# 19_-CAMERA_PWR_CONNECTORS.net
KiCad netlist of a schematic drawn in Altium Designer
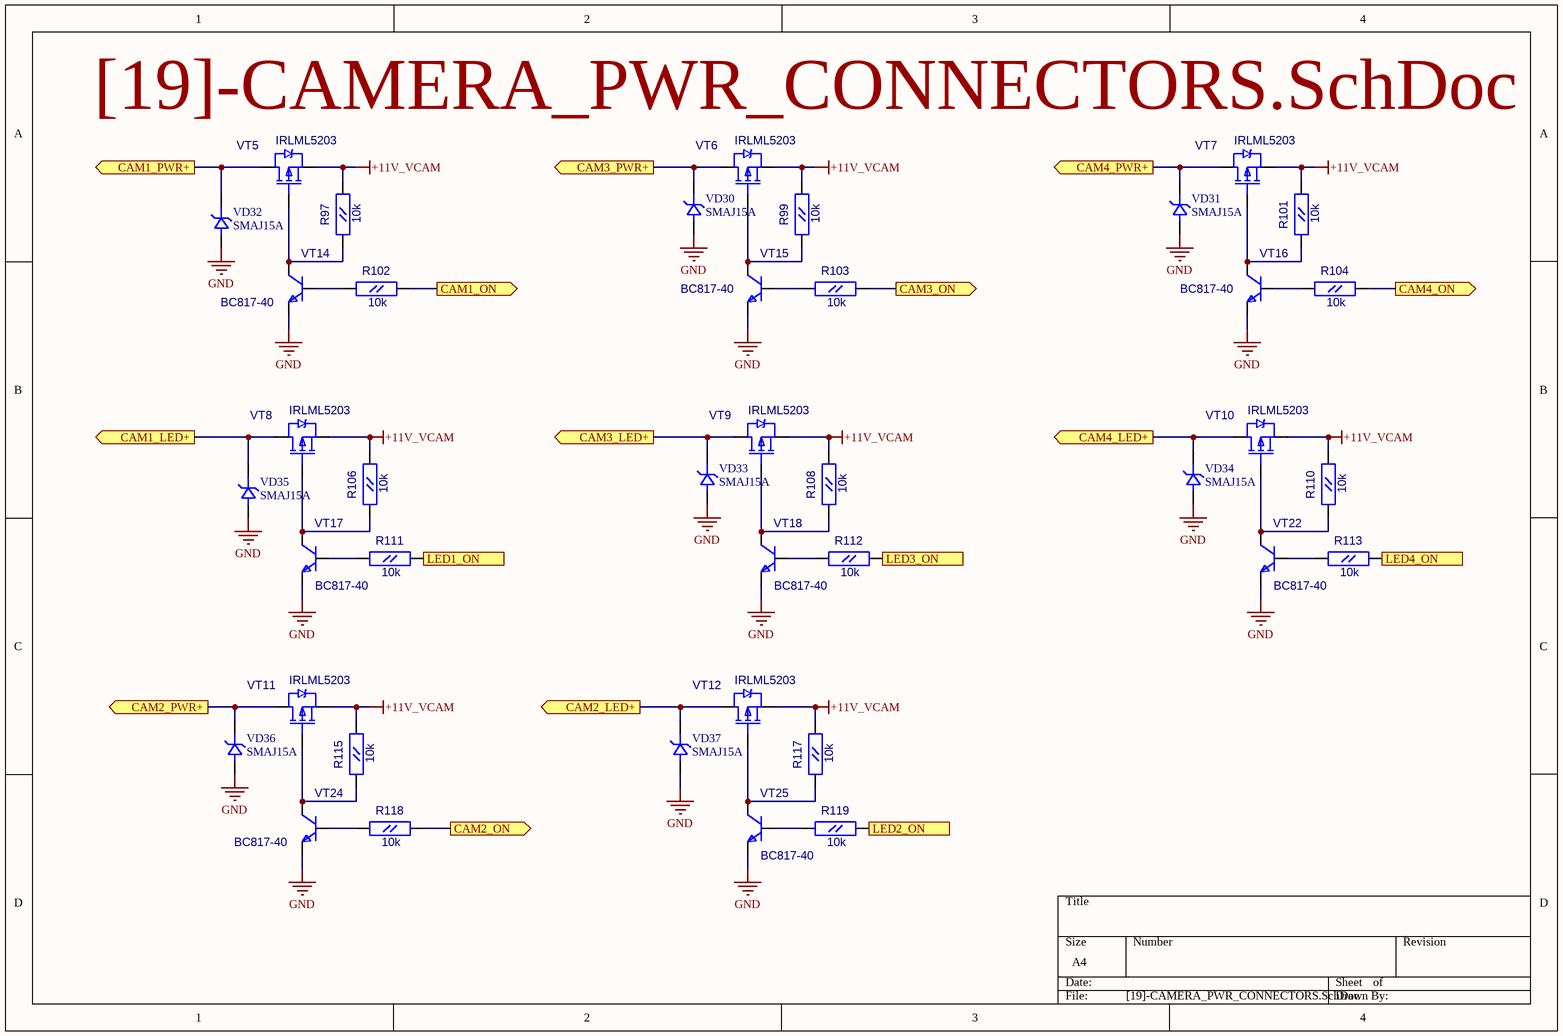
[diagram p0: [19]-CAMERA_PWR_CONNECTORS.SchDoc]

(export (version "E")
  (design (tool "Eeschema 10.0.6"))
  (components
    (comp (ref "R97")
      (value "10k")
      (footprint "RC0603")
      (description "RC0603")
      (libsource (lib "fizik_lib") (part "RC0603"))
    )
    (comp (ref "R99")
      (value "10k")
      (footprint "RC0603")
      (description "RC0603")
      (libsource (lib "fizik_lib") (part "RC0603"))
    )
    (comp (ref "R101")
      (value "10k")
      (footprint "RC0603")
      (description "RC0603")
      (libsource (lib "fizik_lib") (part "RC0603"))
    )
    (comp (ref "R102")
      (value "10k")
      (footprint "RC0603")
      (description "RC0603")
      (libsource (lib "fizik_lib") (part "RC0603"))
    )
    (comp (ref "R103")
      (value "10k")
      (footprint "RC0603")
      (description "RC0603")
      (libsource (lib "fizik_lib") (part "RC0603"))
    )
    (comp (ref "R104")
      (value "10k")
      (footprint "RC0603")
      (description "RC0603")
      (libsource (lib "fizik_lib") (part "RC0603"))
    )
    (comp (ref "R106")
      (value "10k")
      (footprint "RC0603")
      (description "RC0603")
      (libsource (lib "fizik_lib") (part "RC0603"))
    )
    (comp (ref "R108")
      (value "10k")
      (footprint "RC0603")
      (description "RC0603")
      (libsource (lib "fizik_lib") (part "RC0603"))
    )
    (comp (ref "R110")
      (value "10k")
      (footprint "RC0603")
      (description "RC0603")
      (libsource (lib "fizik_lib") (part "RC0603"))
    )
    (comp (ref "R111")
      (value "10k")
      (footprint "RC0603")
      (description "RC0603")
      (libsource (lib "fizik_lib") (part "RC0603"))
    )
    (comp (ref "R112")
      (value "10k")
      (footprint "RC0603")
      (description "RC0603")
      (libsource (lib "fizik_lib") (part "RC0603"))
    )
    (comp (ref "R113")
      (value "10k")
      (footprint "RC0603")
      (description "RC0603")
      (libsource (lib "fizik_lib") (part "RC0603"))
    )
    (comp (ref "R115")
      (value "10k")
      (footprint "RC0603")
      (description "RC0603")
      (libsource (lib "fizik_lib") (part "RC0603"))
    )
    (comp (ref "R117")
      (value "10k")
      (footprint "RC0603")
      (description "RC0603")
      (libsource (lib "fizik_lib") (part "RC0603"))
    )
    (comp (ref "R118")
      (value "10k")
      (footprint "RC0603")
      (description "RC0603")
      (libsource (lib "fizik_lib") (part "RC0603"))
    )
    (comp (ref "R119")
      (value "10k")
      (footprint "RC0603")
      (description "RC0603")
      (libsource (lib "fizik_lib") (part "RC0603"))
    )
    (comp (ref "VD30") (value "SMAJ15A") (footprint "SMA") (libsource (lib "fizik_lib (1)") (part "SMAJ")))
    (comp (ref "VD31") (value "SMAJ15A") (footprint "SMA") (libsource (lib "fizik_lib (1)") (part "SMAJ")))
    (comp (ref "VD32") (value "SMAJ15A") (footprint "SMA") (libsource (lib "fizik_lib (1)") (part "SMAJ")))
    (comp (ref "VD33") (value "SMAJ15A") (footprint "SMA") (libsource (lib "fizik_lib (1)") (part "SMAJ")))
    (comp (ref "VD34") (value "SMAJ15A") (footprint "SMA") (libsource (lib "fizik_lib (1)") (part "SMAJ")))
    (comp (ref "VD35") (value "SMAJ15A") (footprint "SMA") (libsource (lib "fizik_lib (1)") (part "SMAJ")))
    (comp (ref "VD36") (value "SMAJ15A") (footprint "SMA") (libsource (lib "fizik_lib (1)") (part "SMAJ")))
    (comp (ref "VD37") (value "SMAJ15A") (footprint "SMA") (libsource (lib "fizik_lib (1)") (part "SMAJ")))
    (comp (ref "VT5")
      (value "IRLML5203")
      (footprint "SOT-23(123)")
      (description "HEXFET Power MOSFET")
      (libsource (lib "fizik_lib (1)") (part "IRLML6402"))
    )
    (comp (ref "VT6")
      (value "IRLML5203")
      (footprint "SOT-23(123)")
      (description "HEXFET Power MOSFET")
      (libsource (lib "fizik_lib (1)") (part "IRLML6402"))
    )
    (comp (ref "VT7")
      (value "IRLML5203")
      (footprint "SOT-23(123)")
      (description "HEXFET Power MOSFET")
      (libsource (lib "fizik_lib (1)") (part "IRLML6402"))
    )
    (comp (ref "VT8")
      (value "IRLML5203")
      (footprint "SOT-23(123)")
      (description "HEXFET Power MOSFET")
      (libsource (lib "fizik_lib (1)") (part "IRLML6402"))
    )
    (comp (ref "VT9")
      (value "IRLML5203")
      (footprint "SOT-23(123)")
      (description "HEXFET Power MOSFET")
      (libsource (lib "fizik_lib (1)") (part "IRLML6402"))
    )
    (comp (ref "VT10")
      (value "IRLML5203")
      (footprint "SOT-23(123)")
      (description "HEXFET Power MOSFET")
      (libsource (lib "fizik_lib (1)") (part "IRLML6402"))
    )
    (comp (ref "VT11")
      (value "IRLML5203")
      (footprint "SOT-23(123)")
      (description "HEXFET Power MOSFET")
      (libsource (lib "fizik_lib (1)") (part "IRLML6402"))
    )
    (comp (ref "VT12")
      (value "IRLML5203")
      (footprint "SOT-23(123)")
      (description "HEXFET Power MOSFET")
      (libsource (lib "fizik_lib (1)") (part "IRLML6402"))
    )
    (comp (ref "VT14")
      (value "BC817-40")
      (footprint "SOT-23(123)")
      (description "NPN 500ma transistor")
      (libsource (lib "fizik_lib") (part "BC846BLT1"))
    )
    (comp (ref "VT15")
      (value "BC817-40")
      (footprint "SOT-23(123)")
      (description "NPN 500ma transistor")
      (libsource (lib "fizik_lib") (part "BC846BLT1"))
    )
    (comp (ref "VT16")
      (value "BC817-40")
      (footprint "SOT-23(123)")
      (description "NPN 500ma transistor")
      (libsource (lib "fizik_lib") (part "BC846BLT1"))
    )
    (comp (ref "VT17")
      (value "BC817-40")
      (footprint "SOT-23(123)")
      (description "NPN 500ma transistor")
      (libsource (lib "fizik_lib") (part "BC846BLT1"))
    )
    (comp (ref "VT18")
      (value "BC817-40")
      (footprint "SOT-23(123)")
      (description "NPN 500ma transistor")
      (libsource (lib "fizik_lib") (part "BC846BLT1"))
    )
    (comp (ref "VT22")
      (value "BC817-40")
      (footprint "SOT-23(123)")
      (description "NPN 500ma transistor")
      (libsource (lib "fizik_lib") (part "BC846BLT1"))
    )
    (comp (ref "VT24")
      (value "BC817-40")
      (footprint "SOT-23(123)")
      (description "NPN 500ma transistor")
      (libsource (lib "fizik_lib") (part "BC846BLT1"))
    )
    (comp (ref "VT25")
      (value "BC817-40")
      (footprint "SOT-23(123)")
      (description "NPN 500ma transistor")
      (libsource (lib "fizik_lib") (part "BC846BLT1"))
    )
  )
  (nets
    (net (code "1") (name "+11V_VCAM") (class "Default")
      (node (ref "R101") (pin "2") (pinfunction "B_2") (pintype "passive"))
      (node (ref "R106") (pin "2") (pinfunction "B_2") (pintype "passive"))
      (node (ref "R108") (pin "2") (pinfunction "B_2") (pintype "passive"))
      (node (ref "R110") (pin "2") (pinfunction "B_2") (pintype "passive"))
      (node (ref "R115") (pin "2") (pinfunction "B_2") (pintype "passive"))
      (node (ref "R117") (pin "2") (pinfunction "B_2") (pintype "passive"))
      (node (ref "R97") (pin "2") (pinfunction "B_2") (pintype "passive"))
      (node (ref "R99") (pin "2") (pinfunction "B_2") (pintype "passive"))
      (node (ref "VT10") (pin "2") (pinfunction "S_2") (pintype "passive"))
      (node (ref "VT11") (pin "2") (pinfunction "S_2") (pintype "passive"))
      (node (ref "VT12") (pin "2") (pinfunction "S_2") (pintype "passive"))
      (node (ref "VT5") (pin "2") (pinfunction "S_2") (pintype "passive"))
      (node (ref "VT6") (pin "2") (pinfunction "S_2") (pintype "passive"))
      (node (ref "VT7") (pin "2") (pinfunction "S_2") (pintype "passive"))
      (node (ref "VT8") (pin "2") (pinfunction "S_2") (pintype "passive"))
      (node (ref "VT9") (pin "2") (pinfunction "S_2") (pintype "passive"))
    )
    (net (code "2") (name "/CAM1_LED+") (class "Default")
      (node (ref "VD35") (pin "2") (pinfunction "K_2") (pintype "passive"))
      (node (ref "VT8") (pin "3") (pinfunction "D_3") (pintype "passive"))
    )
    (net (code "3") (name "/CAM1_ON") (class "Default")
      (node (ref "R102") (pin "2") (pinfunction "B_2") (pintype "passive"))
    )
    (net (code "4") (name "/CAM1_PWR+") (class "Default")
      (node (ref "VD32") (pin "2") (pinfunction "K_2") (pintype "passive"))
      (node (ref "VT5") (pin "3") (pinfunction "D_3") (pintype "passive"))
    )
    (net (code "5") (name "/CAM2_LED+") (class "Default")
      (node (ref "VD37") (pin "2") (pinfunction "K_2") (pintype "passive"))
      (node (ref "VT12") (pin "3") (pinfunction "D_3") (pintype "passive"))
    )
    (net (code "6") (name "/CAM2_ON") (class "Default")
      (node (ref "R118") (pin "2") (pinfunction "B_2") (pintype "passive"))
    )
    (net (code "7") (name "/CAM2_PWR+") (class "Default")
      (node (ref "VD36") (pin "2") (pinfunction "K_2") (pintype "passive"))
      (node (ref "VT11") (pin "3") (pinfunction "D_3") (pintype "passive"))
    )
    (net (code "8") (name "/CAM3_LED+") (class "Default")
      (node (ref "VD33") (pin "2") (pinfunction "K_2") (pintype "passive"))
      (node (ref "VT9") (pin "3") (pinfunction "D_3") (pintype "passive"))
    )
    (net (code "9") (name "/CAM3_ON") (class "Default")
      (node (ref "R103") (pin "2") (pinfunction "B_2") (pintype "passive"))
    )
    (net (code "10") (name "/CAM3_PWR+") (class "Default")
      (node (ref "VD30") (pin "2") (pinfunction "K_2") (pintype "passive"))
      (node (ref "VT6") (pin "3") (pinfunction "D_3") (pintype "passive"))
    )
    (net (code "11") (name "/CAM4_LED+") (class "Default")
      (node (ref "VD34") (pin "2") (pinfunction "K_2") (pintype "passive"))
      (node (ref "VT10") (pin "3") (pinfunction "D_3") (pintype "passive"))
    )
    (net (code "12") (name "/CAM4_ON") (class "Default")
      (node (ref "R104") (pin "2") (pinfunction "B_2") (pintype "passive"))
    )
    (net (code "13") (name "/CAM4_PWR+") (class "Default")
      (node (ref "VD31") (pin "2") (pinfunction "K_2") (pintype "passive"))
      (node (ref "VT7") (pin "3") (pinfunction "D_3") (pintype "passive"))
    )
    (net (code "14") (name "/LED1_ON") (class "Default")
      (node (ref "R111") (pin "2") (pinfunction "B_2") (pintype "passive"))
    )
    (net (code "15") (name "/LED2_ON") (class "Default")
      (node (ref "R119") (pin "2") (pinfunction "B_2") (pintype "passive"))
    )
    (net (code "16") (name "/LED3_ON") (class "Default")
      (node (ref "R112") (pin "2") (pinfunction "B_2") (pintype "passive"))
    )
    (net (code "17") (name "/LED4_ON") (class "Default")
      (node (ref "R113") (pin "2") (pinfunction "B_2") (pintype "passive"))
    )
    (net (code "18") (name "GND") (class "Default")
      (node (ref "VD30") (pin "1") (pinfunction "A_1") (pintype "passive"))
      (node (ref "VD31") (pin "1") (pinfunction "A_1") (pintype "passive"))
      (node (ref "VD32") (pin "1") (pinfunction "A_1") (pintype "passive"))
      (node (ref "VD33") (pin "1") (pinfunction "A_1") (pintype "passive"))
      (node (ref "VD34") (pin "1") (pinfunction "A_1") (pintype "passive"))
      (node (ref "VD35") (pin "1") (pinfunction "A_1") (pintype "passive"))
      (node (ref "VD36") (pin "1") (pinfunction "A_1") (pintype "passive"))
      (node (ref "VD37") (pin "1") (pinfunction "A_1") (pintype "passive"))
      (node (ref "VT14") (pin "2") (pinfunction "E_2") (pintype "passive"))
      (node (ref "VT15") (pin "2") (pinfunction "E_2") (pintype "passive"))
      (node (ref "VT16") (pin "2") (pinfunction "E_2") (pintype "passive"))
      (node (ref "VT17") (pin "2") (pinfunction "E_2") (pintype "passive"))
      (node (ref "VT18") (pin "2") (pinfunction "E_2") (pintype "passive"))
      (node (ref "VT22") (pin "2") (pinfunction "E_2") (pintype "passive"))
      (node (ref "VT24") (pin "2") (pinfunction "E_2") (pintype "passive"))
      (node (ref "VT25") (pin "2") (pinfunction "E_2") (pintype "passive"))
    )
    (net (code "19") (name "Net-(R97-A)") (class "Default")
      (node (ref "R97") (pin "1") (pinfunction "A_1") (pintype "passive"))
      (node (ref "VT14") (pin "3") (pinfunction "C_3") (pintype "passive"))
      (node (ref "VT5") (pin "1") (pinfunction "G_1") (pintype "passive"))
    )
    (net (code "20") (name "Net-(R99-A)") (class "Default")
      (node (ref "R99") (pin "1") (pinfunction "A_1") (pintype "passive"))
      (node (ref "VT15") (pin "3") (pinfunction "C_3") (pintype "passive"))
      (node (ref "VT6") (pin "1") (pinfunction "G_1") (pintype "passive"))
    )
    (net (code "21") (name "Net-(R101-A)") (class "Default")
      (node (ref "R101") (pin "1") (pinfunction "A_1") (pintype "passive"))
      (node (ref "VT16") (pin "3") (pinfunction "C_3") (pintype "passive"))
      (node (ref "VT7") (pin "1") (pinfunction "G_1") (pintype "passive"))
    )
    (net (code "22") (name "Net-(R102-A)") (class "Default")
      (node (ref "R102") (pin "1") (pinfunction "A_1") (pintype "passive"))
      (node (ref "VT14") (pin "1") (pinfunction "B_1") (pintype "passive"))
    )
    (net (code "23") (name "Net-(R103-A)") (class "Default")
      (node (ref "R103") (pin "1") (pinfunction "A_1") (pintype "passive"))
      (node (ref "VT15") (pin "1") (pinfunction "B_1") (pintype "passive"))
    )
    (net (code "24") (name "Net-(R104-A)") (class "Default")
      (node (ref "R104") (pin "1") (pinfunction "A_1") (pintype "passive"))
      (node (ref "VT16") (pin "1") (pinfunction "B_1") (pintype "passive"))
    )
    (net (code "25") (name "Net-(R106-A)") (class "Default")
      (node (ref "R106") (pin "1") (pinfunction "A_1") (pintype "passive"))
      (node (ref "VT17") (pin "3") (pinfunction "C_3") (pintype "passive"))
      (node (ref "VT8") (pin "1") (pinfunction "G_1") (pintype "passive"))
    )
    (net (code "26") (name "Net-(R108-A)") (class "Default")
      (node (ref "R108") (pin "1") (pinfunction "A_1") (pintype "passive"))
      (node (ref "VT18") (pin "3") (pinfunction "C_3") (pintype "passive"))
      (node (ref "VT9") (pin "1") (pinfunction "G_1") (pintype "passive"))
    )
    (net (code "27") (name "Net-(R110-A)") (class "Default")
      (node (ref "R110") (pin "1") (pinfunction "A_1") (pintype "passive"))
      (node (ref "VT10") (pin "1") (pinfunction "G_1") (pintype "passive"))
      (node (ref "VT22") (pin "3") (pinfunction "C_3") (pintype "passive"))
    )
    (net (code "28") (name "Net-(R111-A)") (class "Default")
      (node (ref "R111") (pin "1") (pinfunction "A_1") (pintype "passive"))
      (node (ref "VT17") (pin "1") (pinfunction "B_1") (pintype "passive"))
    )
    (net (code "29") (name "Net-(R112-A)") (class "Default")
      (node (ref "R112") (pin "1") (pinfunction "A_1") (pintype "passive"))
      (node (ref "VT18") (pin "1") (pinfunction "B_1") (pintype "passive"))
    )
    (net (code "30") (name "Net-(R113-A)") (class "Default")
      (node (ref "R113") (pin "1") (pinfunction "A_1") (pintype "passive"))
      (node (ref "VT22") (pin "1") (pinfunction "B_1") (pintype "passive"))
    )
    (net (code "31") (name "Net-(R115-A)") (class "Default")
      (node (ref "R115") (pin "1") (pinfunction "A_1") (pintype "passive"))
      (node (ref "VT11") (pin "1") (pinfunction "G_1") (pintype "passive"))
      (node (ref "VT24") (pin "3") (pinfunction "C_3") (pintype "passive"))
    )
    (net (code "32") (name "Net-(R117-A)") (class "Default")
      (node (ref "R117") (pin "1") (pinfunction "A_1") (pintype "passive"))
      (node (ref "VT12") (pin "1") (pinfunction "G_1") (pintype "passive"))
      (node (ref "VT25") (pin "3") (pinfunction "C_3") (pintype "passive"))
    )
    (net (code "33") (name "Net-(R118-A)") (class "Default")
      (node (ref "R118") (pin "1") (pinfunction "A_1") (pintype "passive"))
      (node (ref "VT24") (pin "1") (pinfunction "B_1") (pintype "passive"))
    )
    (net (code "34") (name "Net-(R119-A)") (class "Default")
      (node (ref "R119") (pin "1") (pinfunction "A_1") (pintype "passive"))
      (node (ref "VT25") (pin "1") (pinfunction "B_1") (pintype "passive"))
    )
  )
)
